# core5.net
KiCad netlist of a schematic drawn in EAGLE
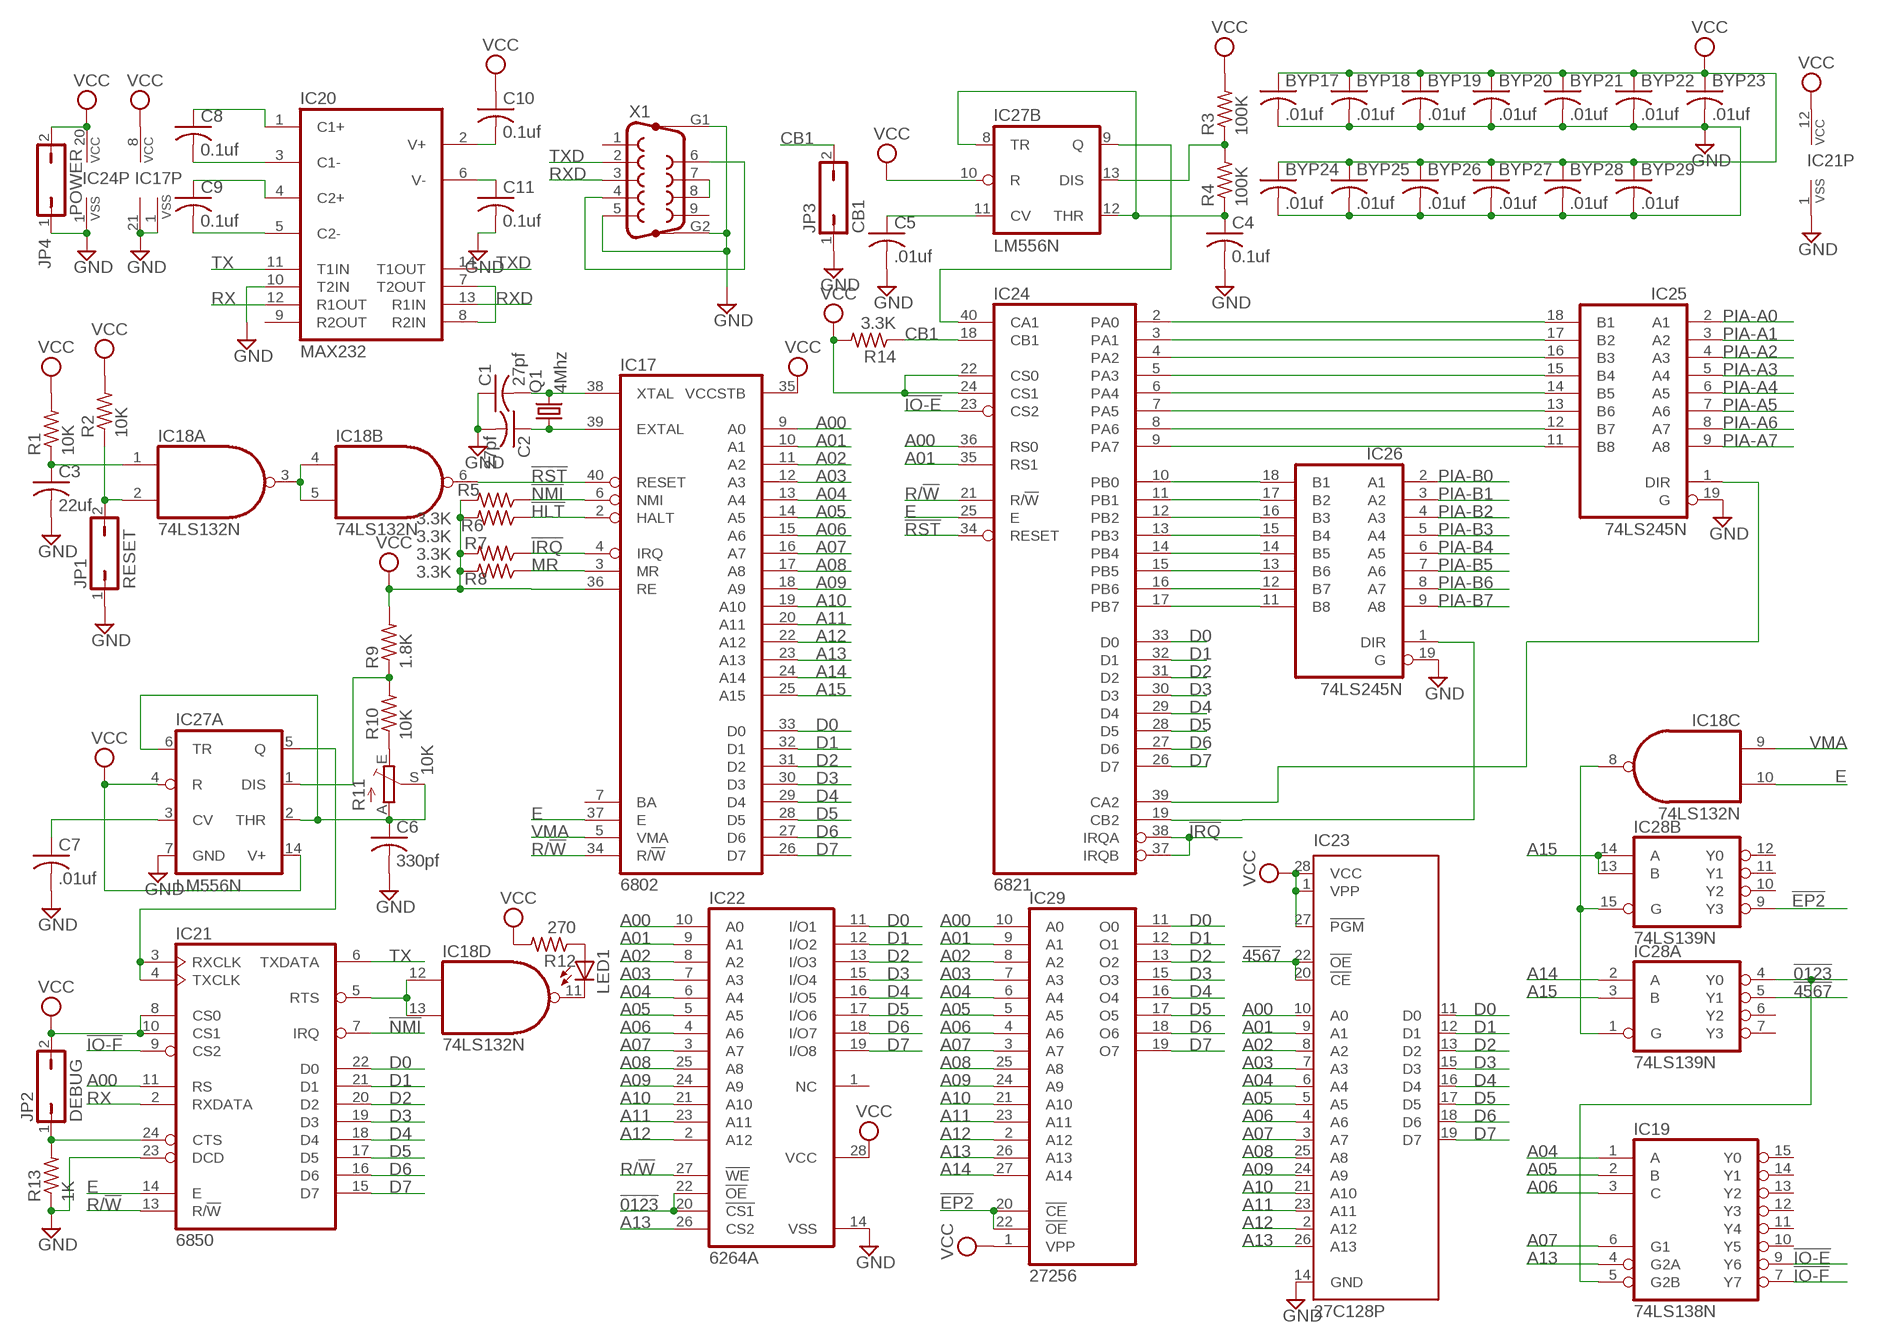
[diagram p0: schematic, sheet 1]
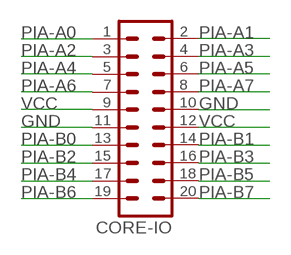
[diagram p1: schematic, sheet 2]

(export (version "E")
  (design (tool "Eeschema 10.0.6"))
  (components
    (comp (ref "CORE-IO")
      (value "MA10-2")
      (footprint "eagle-import:MA10-2")
      (libsource (lib "eagle-import") (part "MA10-2"))
    )
    (comp (ref "BYP17")
      (value ".01uf")
      (footprint "eagle-import:C050-025X075")
      (libsource (lib "eagle-import") (part "C-US050-025X075"))
    )
    (comp (ref "BYP18")
      (value ".01uf")
      (footprint "eagle-import:C050-025X075")
      (libsource (lib "eagle-import") (part "C-US050-025X075"))
    )
    (comp (ref "BYP19")
      (value ".01uf")
      (footprint "eagle-import:C050-025X075")
      (libsource (lib "eagle-import") (part "C-US050-025X075"))
    )
    (comp (ref "BYP20")
      (value ".01uf")
      (footprint "eagle-import:C050-025X075")
      (libsource (lib "eagle-import") (part "C-US050-025X075"))
    )
    (comp (ref "BYP21")
      (value ".01uf")
      (footprint "eagle-import:C050-025X075")
      (libsource (lib "eagle-import") (part "C-US050-025X075"))
    )
    (comp (ref "BYP22")
      (value ".01uf")
      (footprint "eagle-import:C050-025X075")
      (libsource (lib "eagle-import") (part "C-US050-025X075"))
    )
    (comp (ref "BYP23")
      (value ".01uf")
      (footprint "eagle-import:C050-025X075")
      (libsource (lib "eagle-import") (part "C-US050-025X075"))
    )
    (comp (ref "BYP24")
      (value ".01uf")
      (footprint "eagle-import:C050-025X075")
      (libsource (lib "eagle-import") (part "C-US050-025X075"))
    )
    (comp (ref "BYP25")
      (value ".01uf")
      (footprint "eagle-import:C050-025X075")
      (libsource (lib "eagle-import") (part "C-US050-025X075"))
    )
    (comp (ref "BYP26")
      (value ".01uf")
      (footprint "eagle-import:C050-025X075")
      (libsource (lib "eagle-import") (part "C-US050-025X075"))
    )
    (comp (ref "BYP27")
      (value ".01uf")
      (footprint "eagle-import:C050-025X075")
      (libsource (lib "eagle-import") (part "C-US050-025X075"))
    )
    (comp (ref "BYP28")
      (value ".01uf")
      (footprint "eagle-import:C050-025X075")
      (libsource (lib "eagle-import") (part "C-US050-025X075"))
    )
    (comp (ref "BYP29")
      (value ".01uf")
      (footprint "eagle-import:C050-025X075")
      (libsource (lib "eagle-import") (part "C-US050-025X075"))
    )
    (comp (ref "C1")
      (value "27pf")
      (footprint "eagle-import:C050-025X075")
      (libsource (lib "eagle-import") (part "C-US050-025X075"))
    )
    (comp (ref "C2")
      (value "27pf")
      (footprint "eagle-import:C050-025X075")
      (libsource (lib "eagle-import") (part "C-US050-025X075"))
    )
    (comp (ref "C3")
      (value "22uf")
      (footprint "eagle-import:C102-043X133")
      (libsource (lib "eagle-import") (part "C-US102-043X133"))
    )
    (comp (ref "C4")
      (value "0.1uf")
      (footprint "eagle-import:C050-025X075")
      (libsource (lib "eagle-import") (part "C-US050-025X075"))
    )
    (comp (ref "C5")
      (value ".01uf")
      (footprint "eagle-import:C050-025X075")
      (libsource (lib "eagle-import") (part "C-US050-025X075"))
    )
    (comp (ref "C6")
      (value "330pf")
      (footprint "eagle-import:C050-025X075")
      (libsource (lib "eagle-import") (part "C-US050-025X075"))
    )
    (comp (ref "C7")
      (value ".01uf")
      (footprint "eagle-import:C050-025X075")
      (libsource (lib "eagle-import") (part "C-US050-025X075"))
    )
    (comp (ref "C8")
      (value "0.1uf")
      (footprint "eagle-import:C050-025X075")
      (libsource (lib "eagle-import") (part "C-US050-025X075"))
    )
    (comp (ref "C9")
      (value "0.1uf")
      (footprint "eagle-import:C050-025X075")
      (libsource (lib "eagle-import") (part "C-US050-025X075"))
    )
    (comp (ref "C10")
      (value "0.1uf")
      (footprint "eagle-import:C050-025X075")
      (libsource (lib "eagle-import") (part "C-US050-025X075"))
    )
    (comp (ref "C11")
      (value "0.1uf")
      (footprint "eagle-import:C050-025X075")
      (libsource (lib "eagle-import") (part "C-US050-025X075"))
    )
    (comp (ref "IC17")
      (value "6802")
      (footprint "eagle-import:DIL40")
      (libsource (lib "eagle-import") (part "6802"))
    )
    (comp (ref "IC18")
      (value "74LS132N")
      (footprint "eagle-import:DIL14")
      (libsource (lib "eagle-import") (part "7400NLS"))
    )
    (comp (ref "IC19")
      (value "74LS138N")
      (footprint "eagle-import:DIL16")
      (libsource (lib "eagle-import") (part "74138NLS"))
    )
    (comp (ref "IC20")
      (value "MAX232")
      (footprint "eagle-import:DIL16")
      (fields (field (name "MF") "MAXIM") (field (name "MPN") "MAX232ACPE+"))
      (libsource (lib "eagle-import") (part "MAX232"))
    )
    (comp (ref "IC21")
      (value "6850")
      (footprint "eagle-import:DIL24")
      (fields (field (name "MF") "NTE ELECTRONICS") (field (name "MPN") "NTE6850"))
      (libsource (lib "eagle-import") (part "6850"))
    )
    (comp (ref "IC22")
      (value "6264A")
      (footprint "eagle-import:DIL28-6")
      (libsource (lib "eagle-import") (part "6264A"))
    )
    (comp (ref "IC23")
      (value "27C128P")
      (footprint "eagle-import:DIL28-6")
      (libsource (lib "eagle-import") (part "27128PC"))
    )
    (comp (ref "IC24")
      (value "6821")
      (footprint "eagle-import:DIL40")
      (fields (field (name "MF") "NTE ELECTRONICS") (field (name "MPN") "NTE6821"))
      (libsource (lib "eagle-import") (part "6821"))
    )
    (comp (ref "IC25")
      (value "74LS245N")
      (footprint "eagle-import:DIL20")
      (libsource (lib "eagle-import") (part "74245NLS"))
    )
    (comp (ref "IC26")
      (value "74LS245N")
      (footprint "eagle-import:DIL20")
      (libsource (lib "eagle-import") (part "74245NLS"))
    )
    (comp (ref "IC27")
      (value "LM556N")
      (footprint "eagle-import:DIL14")
      (libsource (lib "eagle-import") (part "556NLM"))
    )
    (comp (ref "IC28")
      (value "74LS139N")
      (footprint "eagle-import:DIL16")
      (libsource (lib "eagle-import") (part "74139NLS"))
    )
    (comp (ref "IC29")
      (value "27256")
      (footprint "eagle-import:DIL28")
      (libsource (lib "eagle-import") (part "27256"))
    )
    (comp (ref "JP1")
      (value "RESET")
      (footprint "eagle-import:JP1")
      (libsource (lib "eagle-import") (part "JP1Q"))
    )
    (comp (ref "JP2")
      (value "DEBUG")
      (footprint "eagle-import:JP1")
      (libsource (lib "eagle-import") (part "JP1Q"))
    )
    (comp (ref "JP3")
      (value "CB1")
      (footprint "eagle-import:JP1")
      (libsource (lib "eagle-import") (part "JP1Q"))
    )
    (comp (ref "JP4")
      (value "POWER")
      (footprint "eagle-import:JP1")
      (libsource (lib "eagle-import") (part "JP1Q"))
    )
    (comp (ref "LED1")
      (value "LED3MM")
      (footprint "eagle-import:LED3MM")
      (libsource (lib "eagle-import") (part "LED3MM"))
    )
    (comp (ref "Q1")
      (value "4Mhz")
      (footprint "eagle-import:HC18U-V")
      (libsource (lib "eagle-import") (part "CRYSTALHC18U-V"))
    )
    (comp (ref "R1")
      (value "10K")
      (footprint "eagle-import:0207_7")
      (libsource (lib "eagle-import") (part "R-US_0207/7"))
    )
    (comp (ref "R2")
      (value "10K")
      (footprint "eagle-import:0207_7")
      (libsource (lib "eagle-import") (part "R-US_0207/7"))
    )
    (comp (ref "R3")
      (value "100K")
      (footprint "eagle-import:0207_7")
      (libsource (lib "eagle-import") (part "R-US_0207/7"))
    )
    (comp (ref "R4")
      (value "100K")
      (footprint "eagle-import:0207_7")
      (libsource (lib "eagle-import") (part "R-US_0207/7"))
    )
    (comp (ref "R5")
      (value "3.3K")
      (footprint "eagle-import:0207_7")
      (libsource (lib "eagle-import") (part "R-US_0207/7"))
    )
    (comp (ref "R6")
      (value "3.3K")
      (footprint "eagle-import:0207_7")
      (libsource (lib "eagle-import") (part "R-US_0207/7"))
    )
    (comp (ref "R7")
      (value "3.3K")
      (footprint "eagle-import:0207_7")
      (libsource (lib "eagle-import") (part "R-US_0207/7"))
    )
    (comp (ref "R8")
      (value "3.3K")
      (footprint "eagle-import:0207_7")
      (libsource (lib "eagle-import") (part "R-US_0207/7"))
    )
    (comp (ref "R9")
      (value "1.8K")
      (footprint "eagle-import:0207_7")
      (libsource (lib "eagle-import") (part "R-US_0207/7"))
    )
    (comp (ref "R10")
      (value "10K")
      (footprint "eagle-import:0207_7")
      (libsource (lib "eagle-import") (part "R-US_0207/7"))
    )
    (comp (ref "R11")
      (value "10K")
      (footprint "eagle-import:SP19L")
      (libsource (lib "eagle-import") (part "TRIM_EU-B90P"))
    )
    (comp (ref "R12")
      (value "270")
      (footprint "eagle-import:0207_7")
      (libsource (lib "eagle-import") (part "R-US_0207/7"))
    )
    (comp (ref "R13")
      (value "1K")
      (footprint "eagle-import:0207_7")
      (libsource (lib "eagle-import") (part "R-US_0207/7"))
    )
    (comp (ref "R14")
      (value "3.3K")
      (footprint "eagle-import:0207_7")
      (libsource (lib "eagle-import") (part "R-US_0207/7"))
    )
    (comp (ref "X1")
      (value "F09HP")
      (footprint "eagle-import:F09HP")
      (libsource (lib "eagle-import") (part "F09HP"))
    )
  )
  (nets
    (net (code "1") (name "A00") (class "Default")
      (node (ref "IC17") (pin "9") (pinfunction "A0_9") (pintype "output"))
      (node (ref "IC21") (pin "11") (pinfunction "RS_11") (pintype "input"))
      (node (ref "IC22") (pin "10") (pinfunction "A0_10") (pintype "input"))
      (node (ref "IC23") (pin "10") (pinfunction "A0_10") (pintype "input"))
      (node (ref "IC24") (pin "36") (pinfunction "RS0_36") (pintype "input"))
      (node (ref "IC29") (pin "10") (pinfunction "A0_10") (pintype "input"))
    )
    (net (code "2") (name "A01") (class "Default")
      (node (ref "IC17") (pin "10") (pinfunction "A1_10") (pintype "output"))
      (node (ref "IC22") (pin "9") (pinfunction "A1_9") (pintype "input"))
      (node (ref "IC23") (pin "9") (pinfunction "A1_9") (pintype "input"))
      (node (ref "IC24") (pin "35") (pinfunction "RS1_35") (pintype "input"))
      (node (ref "IC29") (pin "9") (pinfunction "A1_9") (pintype "input"))
    )
    (net (code "3") (name "A02") (class "Default")
      (node (ref "IC17") (pin "11") (pinfunction "A2_11") (pintype "output"))
      (node (ref "IC22") (pin "8") (pinfunction "A2_8") (pintype "input"))
      (node (ref "IC23") (pin "8") (pinfunction "A2_8") (pintype "input"))
      (node (ref "IC29") (pin "8") (pinfunction "A2_8") (pintype "input"))
    )
    (net (code "4") (name "A03") (class "Default")
      (node (ref "IC17") (pin "12") (pinfunction "A3_12") (pintype "output"))
      (node (ref "IC22") (pin "7") (pinfunction "A3_7") (pintype "input"))
      (node (ref "IC23") (pin "7") (pinfunction "A3_7") (pintype "input"))
      (node (ref "IC29") (pin "7") (pinfunction "A3_7") (pintype "input"))
    )
    (net (code "5") (name "A04") (class "Default")
      (node (ref "IC17") (pin "13") (pinfunction "A4_13") (pintype "output"))
      (node (ref "IC19") (pin "1") (pinfunction "A_1") (pintype "input"))
      (node (ref "IC22") (pin "6") (pinfunction "A4_6") (pintype "input"))
      (node (ref "IC23") (pin "6") (pinfunction "A4_6") (pintype "input"))
      (node (ref "IC29") (pin "6") (pinfunction "A4_6") (pintype "input"))
    )
    (net (code "6") (name "A05") (class "Default")
      (node (ref "IC17") (pin "14") (pinfunction "A5_14") (pintype "output"))
      (node (ref "IC19") (pin "2") (pinfunction "B_2") (pintype "input"))
      (node (ref "IC22") (pin "5") (pinfunction "A5_5") (pintype "input"))
      (node (ref "IC23") (pin "5") (pinfunction "A5_5") (pintype "input"))
      (node (ref "IC29") (pin "5") (pinfunction "A5_5") (pintype "input"))
    )
    (net (code "7") (name "A06") (class "Default")
      (node (ref "IC17") (pin "15") (pinfunction "A6_15") (pintype "output"))
      (node (ref "IC19") (pin "3") (pinfunction "C_3") (pintype "input"))
      (node (ref "IC22") (pin "4") (pinfunction "A6_4") (pintype "input"))
      (node (ref "IC23") (pin "4") (pinfunction "A6_4") (pintype "input"))
      (node (ref "IC29") (pin "4") (pinfunction "A6_4") (pintype "input"))
    )
    (net (code "8") (name "A07") (class "Default")
      (node (ref "IC17") (pin "16") (pinfunction "A7_16") (pintype "output"))
      (node (ref "IC19") (pin "6") (pinfunction "G1_6") (pintype "input"))
      (node (ref "IC22") (pin "3") (pinfunction "A7_3") (pintype "input"))
      (node (ref "IC23") (pin "3") (pinfunction "A7_3") (pintype "input"))
      (node (ref "IC29") (pin "3") (pinfunction "A7_3") (pintype "input"))
    )
    (net (code "9") (name "A08") (class "Default")
      (node (ref "IC17") (pin "17") (pinfunction "A8_17") (pintype "output"))
      (node (ref "IC22") (pin "25") (pinfunction "A8_25") (pintype "input"))
      (node (ref "IC23") (pin "25") (pinfunction "A8_25") (pintype "input"))
      (node (ref "IC29") (pin "25") (pinfunction "A8_25") (pintype "input"))
    )
    (net (code "10") (name "A09") (class "Default")
      (node (ref "IC17") (pin "18") (pinfunction "A9_18") (pintype "output"))
      (node (ref "IC22") (pin "24") (pinfunction "A9_24") (pintype "input"))
      (node (ref "IC23") (pin "24") (pinfunction "A9_24") (pintype "input"))
      (node (ref "IC29") (pin "24") (pinfunction "A9_24") (pintype "input"))
    )
    (net (code "11") (name "A10") (class "Default")
      (node (ref "IC17") (pin "19") (pinfunction "A10_19") (pintype "output"))
      (node (ref "IC22") (pin "21") (pinfunction "A10_21") (pintype "input"))
      (node (ref "IC23") (pin "21") (pinfunction "A10_21") (pintype "input"))
      (node (ref "IC29") (pin "21") (pinfunction "A10_21") (pintype "input"))
    )
    (net (code "12") (name "A11") (class "Default")
      (node (ref "IC17") (pin "20") (pinfunction "A11_20") (pintype "output"))
      (node (ref "IC22") (pin "23") (pinfunction "A11_23") (pintype "input"))
      (node (ref "IC23") (pin "23") (pinfunction "A11_23") (pintype "input"))
      (node (ref "IC29") (pin "23") (pinfunction "A11_23") (pintype "input"))
    )
    (net (code "13") (name "A12") (class "Default")
      (node (ref "IC17") (pin "22") (pinfunction "A12_22") (pintype "output"))
      (node (ref "IC22") (pin "2") (pinfunction "A12_2") (pintype "input"))
      (node (ref "IC23") (pin "2") (pinfunction "A12_2") (pintype "input"))
      (node (ref "IC29") (pin "2") (pinfunction "A12_2") (pintype "input"))
    )
    (net (code "14") (name "A13") (class "Default")
      (node (ref "IC17") (pin "23") (pinfunction "A13_23") (pintype "output"))
      (node (ref "IC19") (pin "4") (pinfunction "G2A_4") (pintype "input"))
      (node (ref "IC22") (pin "26") (pinfunction "CS2_26") (pintype "input"))
      (node (ref "IC23") (pin "26") (pinfunction "A13_26") (pintype "input"))
      (node (ref "IC29") (pin "26") (pinfunction "A13_26") (pintype "input"))
    )
    (net (code "15") (name "A14") (class "Default")
      (node (ref "IC17") (pin "24") (pinfunction "A14_24") (pintype "output"))
      (node (ref "IC28") (pin "2") (pinfunction "A_2") (pintype "input"))
      (node (ref "IC29") (pin "27") (pinfunction "A14_27") (pintype "input"))
    )
    (net (code "16") (name "A15") (class "Default")
      (node (ref "IC17") (pin "25") (pinfunction "A15_25") (pintype "output"))
      (node (ref "IC28") (pin "13") (pinfunction "B_13") (pintype "input"))
      (node (ref "IC28") (pin "14") (pinfunction "A_14") (pintype "input"))
      (node (ref "IC28") (pin "3") (pinfunction "B_3") (pintype "input"))
    )
    (net (code "17") (name "CB1") (class "Default")
      (node (ref "IC24") (pin "18") (pinfunction "CB1_18") (pintype "input"))
      (node (ref "JP3") (pin "2") (pinfunction "2_2") (pintype "passive"))
      (node (ref "R14") (pin "1") (pinfunction "1_1") (pintype "passive"))
    )
    (net (code "18") (name "D0") (class "Default")
      (node (ref "IC17") (pin "33") (pinfunction "D0_33") (pintype "bidirectional"))
      (node (ref "IC21") (pin "22") (pinfunction "D0_22") (pintype "bidirectional"))
      (node (ref "IC22") (pin "11") (pinfunction "I/O1_11") (pintype "bidirectional"))
      (node (ref "IC23") (pin "11") (pinfunction "D0_11") (pintype "tri_state"))
      (node (ref "IC24") (pin "33") (pinfunction "D0_33") (pintype "bidirectional"))
      (node (ref "IC29") (pin "11") (pinfunction "O0_11") (pintype "tri_state"))
    )
    (net (code "19") (name "D1") (class "Default")
      (node (ref "IC17") (pin "32") (pinfunction "D1_32") (pintype "bidirectional"))
      (node (ref "IC21") (pin "21") (pinfunction "D1_21") (pintype "bidirectional"))
      (node (ref "IC22") (pin "12") (pinfunction "I/O2_12") (pintype "bidirectional"))
      (node (ref "IC23") (pin "12") (pinfunction "D1_12") (pintype "tri_state"))
      (node (ref "IC24") (pin "32") (pinfunction "D1_32") (pintype "bidirectional"))
      (node (ref "IC29") (pin "12") (pinfunction "O1_12") (pintype "tri_state"))
    )
    (net (code "20") (name "D2") (class "Default")
      (node (ref "IC17") (pin "31") (pinfunction "D2_31") (pintype "bidirectional"))
      (node (ref "IC21") (pin "20") (pinfunction "D2_20") (pintype "bidirectional"))
      (node (ref "IC22") (pin "13") (pinfunction "I/O3_13") (pintype "bidirectional"))
      (node (ref "IC23") (pin "13") (pinfunction "D2_13") (pintype "tri_state"))
      (node (ref "IC24") (pin "31") (pinfunction "D2_31") (pintype "bidirectional"))
      (node (ref "IC29") (pin "13") (pinfunction "O2_13") (pintype "tri_state"))
    )
    (net (code "21") (name "D3") (class "Default")
      (node (ref "IC17") (pin "30") (pinfunction "D3_30") (pintype "bidirectional"))
      (node (ref "IC21") (pin "19") (pinfunction "D3_19") (pintype "bidirectional"))
      (node (ref "IC22") (pin "15") (pinfunction "I/O4_15") (pintype "bidirectional"))
      (node (ref "IC23") (pin "15") (pinfunction "D3_15") (pintype "tri_state"))
      (node (ref "IC24") (pin "30") (pinfunction "D3_30") (pintype "bidirectional"))
      (node (ref "IC29") (pin "15") (pinfunction "O3_15") (pintype "tri_state"))
    )
    (net (code "22") (name "D4") (class "Default")
      (node (ref "IC17") (pin "29") (pinfunction "D4_29") (pintype "bidirectional"))
      (node (ref "IC21") (pin "18") (pinfunction "D4_18") (pintype "bidirectional"))
      (node (ref "IC22") (pin "16") (pinfunction "I/O5_16") (pintype "bidirectional"))
      (node (ref "IC23") (pin "16") (pinfunction "D4_16") (pintype "tri_state"))
      (node (ref "IC24") (pin "29") (pinfunction "D4_29") (pintype "bidirectional"))
      (node (ref "IC29") (pin "16") (pinfunction "O4_16") (pintype "tri_state"))
    )
    (net (code "23") (name "D5") (class "Default")
      (node (ref "IC17") (pin "28") (pinfunction "D5_28") (pintype "bidirectional"))
      (node (ref "IC21") (pin "17") (pinfunction "D5_17") (pintype "bidirectional"))
      (node (ref "IC22") (pin "17") (pinfunction "I/O6_17") (pintype "bidirectional"))
      (node (ref "IC23") (pin "17") (pinfunction "D5_17") (pintype "tri_state"))
      (node (ref "IC24") (pin "28") (pinfunction "D5_28") (pintype "bidirectional"))
      (node (ref "IC29") (pin "17") (pinfunction "O5_17") (pintype "tri_state"))
    )
    (net (code "24") (name "D6") (class "Default")
      (node (ref "IC17") (pin "27") (pinfunction "D6_27") (pintype "bidirectional"))
      (node (ref "IC21") (pin "16") (pinfunction "D6_16") (pintype "bidirectional"))
      (node (ref "IC22") (pin "18") (pinfunction "I/O7_18") (pintype "bidirectional"))
      (node (ref "IC23") (pin "18") (pinfunction "D6_18") (pintype "tri_state"))
      (node (ref "IC24") (pin "27") (pinfunction "D6_27") (pintype "bidirectional"))
      (node (ref "IC29") (pin "18") (pinfunction "O6_18") (pintype "tri_state"))
    )
    (net (code "25") (name "D7") (class "Default")
      (node (ref "IC17") (pin "26") (pinfunction "D7_26") (pintype "bidirectional"))
      (node (ref "IC21") (pin "15") (pinfunction "D7_15") (pintype "bidirectional"))
      (node (ref "IC22") (pin "19") (pinfunction "I/O8_19") (pintype "bidirectional"))
      (node (ref "IC23") (pin "19") (pinfunction "D7_19") (pintype "tri_state"))
      (node (ref "IC24") (pin "26") (pinfunction "D7_26") (pintype "bidirectional"))
      (node (ref "IC29") (pin "19") (pinfunction "O7_19") (pintype "tri_state"))
    )
    (net (code "26") (name "E") (class "Default")
      (node (ref "IC17") (pin "37") (pinfunction "E_37") (pintype "output"))
      (node (ref "IC18") (pin "10") (pinfunction "I1_10") (pintype "input"))
      (node (ref "IC21") (pin "14") (pinfunction "E_14") (pintype "input"))
      (node (ref "IC24") (pin "25") (pinfunction "E_25") (pintype "input"))
    )
    (net (code "27") (name "GND") (class "Default")
      (node (ref "BYP17") (pin "2") (pinfunction "2_2") (pintype "passive"))
      (node (ref "BYP18") (pin "2") (pinfunction "2_2") (pintype "passive"))
      (node (ref "BYP19") (pin "2") (pinfunction "2_2") (pintype "passive"))
      (node (ref "BYP20") (pin "2") (pinfunction "2_2") (pintype "passive"))
      (node (ref "BYP21") (pin "2") (pinfunction "2_2") (pintype "passive"))
      (node (ref "BYP22") (pin "2") (pinfunction "2_2") (pintype "passive"))
      (node (ref "BYP23") (pin "2") (pinfunction "2_2") (pintype "passive"))
      (node (ref "BYP24") (pin "2") (pinfunction "2_2") (pintype "passive"))
      (node (ref "BYP25") (pin "2") (pinfunction "2_2") (pintype "passive"))
      (node (ref "BYP26") (pin "2") (pinfunction "2_2") (pintype "passive"))
      (node (ref "BYP27") (pin "2") (pinfunction "2_2") (pintype "passive"))
      (node (ref "BYP28") (pin "2") (pinfunction "2_2") (pintype "passive"))
      (node (ref "BYP29") (pin "2") (pinfunction "2_2") (pintype "passive"))
      (node (ref "C1") (pin "1") (pinfunction "1_1") (pintype "passive"))
      (node (ref "C11") (pin "2") (pinfunction "2_2") (pintype "passive"))
      (node (ref "C2") (pin "2") (pinfunction "2_2") (pintype "passive"))
      (node (ref "C3") (pin "2") (pinfunction "2_2") (pintype "passive"))
      (node (ref "C4") (pin "2") (pinfunction "2_2") (pintype "passive"))
      (node (ref "C5") (pin "2") (pinfunction "2_2") (pintype "passive"))
      (node (ref "C6") (pin "2") (pinfunction "2_2") (pintype "passive"))
      (node (ref "C7") (pin "2") (pinfunction "2_2") (pintype "passive"))
      (node (ref "CORE-IO") (pin "10") (pinfunction "10_10") (pintype "passive"))
      (node (ref "CORE-IO") (pin "11") (pinfunction "11_11") (pintype "passive"))
      (node (ref "IC17") (pin "1") (pinfunction "VSS_1") (pintype "power_in"))
      (node (ref "IC17") (pin "21") (pinfunction "VSS_21") (pintype "power_in"))
      (node (ref "IC20") (pin "10") (pinfunction "T2IN_10") (pintype "input"))
      (node (ref "IC21") (pin "1") (pinfunction "VSS_1") (pintype "power_in"))
      (node (ref "IC21") (pin "23") (pinfunction "DCD_23") (pintype "input"))
      (node (ref "IC22") (pin "14") (pinfunction "VSS_14") (pintype "power_in"))
      (node (ref "IC23") (pin "14") (pinfunction "GND_14") (pintype "power_in"))
      (node (ref "IC24") (pin "1") (pinfunction "VSS_1") (pintype "power_in"))
      (node (ref "IC25") (pin "19") (pinfunction "G_19") (pintype "input"))
      (node (ref "IC26") (pin "19") (pinfunction "G_19") (pintype "input"))
      (node (ref "IC27") (pin "7") (pinfunction "GND_7") (pintype "power_in"))
      (node (ref "JP1") (pin "1") (pinfunction "1_1") (pintype "passive"))
      (node (ref "JP3") (pin "1") (pinfunction "1_1") (pintype "passive"))
      (node (ref "JP4") (pin "1") (pinfunction "1_1") (pintype "passive"))
      (node (ref "R13") (pin "1") (pinfunction "1_1") (pintype "passive"))
      (node (ref "X1") (pin "5") (pinfunction "5_5") (pintype "passive"))
      (node (ref "X1") (pin "G1") (pinfunction "G1_G1") (pintype "passive"))
      (node (ref "X1") (pin "G2") (pinfunction "G2_G2") (pintype "passive"))
    )
    (net (code "28") (name "MR") (class "Default")
      (node (ref "IC17") (pin "3") (pinfunction "MR_3") (pintype "input"))
      (node (ref "R8") (pin "1") (pinfunction "1_1") (pintype "passive"))
    )
    (net (code "29") (name "Net-(IC17A-EXTAL)") (class "Default")
      (node (ref "C2") (pin "1") (pinfunction "1_1") (pintype "passive"))
      (node (ref "IC17") (pin "39") (pinfunction "EXTAL_39") (pintype "input"))
      (node (ref "Q1") (pin "1") (pinfunction "1_1") (pintype "passive"))
    )
    (net (code "30") (name "Net-(IC17A-XTAL)") (class "Default")
      (node (ref "C1") (pin "2") (pinfunction "2_2") (pintype "passive"))
      (node (ref "IC17") (pin "38") (pinfunction "XTAL_38") (pintype "input"))
      (node (ref "Q1") (pin "2") (pinfunction "2_2") (pintype "passive"))
    )
    (net (code "31") (name "Net-(IC18A-I0)") (class "Default")
      (node (ref "C3") (pin "1") (pinfunction "1_1") (pintype "passive"))
      (node (ref "IC18") (pin "1") (pinfunction "I0_1") (pintype "input"))
      (node (ref "R1") (pin "1") (pinfunction "1_1") (pintype "passive"))
    )
    (net (code "32") (name "Net-(IC18A-I1)") (class "Default")
      (node (ref "IC18") (pin "2") (pinfunction "I1_2") (pintype "input"))
      (node (ref "JP1") (pin "2") (pinfunction "2_2") (pintype "passive"))
      (node (ref "R2") (pin "1") (pinfunction "1_1") (pintype "passive"))
    )
    (net (code "33") (name "Net-(IC18A-O)") (class "Default")
      (node (ref "IC18") (pin "3") (pinfunction "O_3") (pintype "output"))
      (node (ref "IC18") (pin "4") (pinfunction "I0_4") (pintype "input"))
      (node (ref "IC18") (pin "5") (pinfunction "I1_5") (pintype "input"))
    )
    (net (code "34") (name "Net-(IC18C-O)") (class "Default")
      (node (ref "IC18") (pin "8") (pinfunction "O_8") (pintype "output"))
      (node (ref "IC28") (pin "1") (pinfunction "G_1") (pintype "input"))
      (node (ref "IC28") (pin "15") (pinfunction "G_15") (pintype "input"))
    )
    (net (code "35") (name "Net-(IC18D-I0)") (class "Default")
      (node (ref "IC18") (pin "12") (pinfunction "I0_12") (pintype "input"))
      (node (ref "IC18") (pin "13") (pinfunction "I1_13") (pintype "input"))
      (node (ref "IC21") (pin "5") (pinfunction "RTS_5") (pintype "output"))
    )
    (net (code "36") (name "Net-(IC18D-O)") (class "Default")
      (node (ref "IC18") (pin "11") (pinfunction "O_11") (pintype "output"))
      (node (ref "LED1") (pin "K") (pinfunction "C_K") (pintype "passive"))
    )
    (net (code "37") (name "Net-(IC20A-C1+)") (class "Default")
      (node (ref "C8") (pin "1") (pinfunction "1_1") (pintype "passive"))
      (node (ref "IC20") (pin "1") (pinfunction "C1+_1") (pintype "bidirectional"))
    )
    (net (code "38") (name "Net-(IC20A-C1-)") (class "Default")
      (node (ref "C8") (pin "2") (pinfunction "2_2") (pintype "passive"))
      (node (ref "IC20") (pin "3") (pinfunction "C1-_3") (pintype "bidirectional"))
    )
    (net (code "39") (name "Net-(IC20A-C2+)") (class "Default")
      (node (ref "C9") (pin "1") (pinfunction "1_1") (pintype "passive"))
      (node (ref "IC20") (pin "4") (pinfunction "C2+_4") (pintype "bidirectional"))
    )
    (net (code "40") (name "Net-(IC20A-C2-)") (class "Default")
      (node (ref "C9") (pin "2") (pinfunction "2_2") (pintype "passive"))
      (node (ref "IC20") (pin "5") (pinfunction "C2-_5") (pintype "bidirectional"))
    )
    (net (code "41") (name "Net-(IC20A-R2IN)") (class "Default")
      (node (ref "IC20") (pin "7") (pinfunction "T2OUT_7") (pintype "output"))
      (node (ref "IC20") (pin "8") (pinfunction "R2IN_8") (pintype "input"))
    )
    (net (code "42") (name "Net-(IC20A-V+)") (class "Default")
      (node (ref "C10") (pin "2") (pinfunction "2_2") (pintype "passive"))
      (node (ref "IC20") (pin "2") (pinfunction "V+_2") (pintype "bidirectional"))
    )
    (net (code "43") (name "Net-(IC20A-V-)") (class "Default")
      (node (ref "C11") (pin "1") (pinfunction "1_1") (pintype "passive"))
      (node (ref "IC20") (pin "6") (pinfunction "V-_6") (pintype "bidirectional"))
    )
    (net (code "44") (name "Net-(IC21A-CTS)") (class "Default")
      (node (ref "IC21") (pin "24") (pinfunction "CTS_24") (pintype "input"))
      (node (ref "JP2") (pin "1") (pinfunction "1_1") (pintype "passive"))
      (node (ref "R13") (pin "2") (pinfunction "2_2") (pintype "passive"))
    )
    (net (code "45") (name "Net-(IC21A-RXCLK)") (class "Default")
      (node (ref "IC21") (pin "3") (pinfunction "RXCLK_3") (pintype "input"))
      (node (ref "IC21") (pin "4") (pinfunction "TXCLK_4") (pintype "input"))
      (node (ref "IC27") (pin "5") (pinfunction "Q_5") (pintype "output"))
    )
    (net (code "46") (name "Net-(IC24A-CA1)") (class "Default")
      (node (ref "IC24") (pin "40") (pinfunction "CA1_40") (pintype "input"))
      (node (ref "IC27") (pin "9") (pinfunction "Q_9") (pintype "output"))
    )
    (net (code "47") (name "Net-(IC24A-CA2)") (class "Default")
      (node (ref "IC24") (pin "39") (pinfunction "CA2_39") (pintype "bidirectional"))
      (node (ref "IC25") (pin "1") (pinfunction "DIR_1") (pintype "input"))
    )
    (net (code "48") (name "Net-(IC24A-CB2)") (class "Default")
      (node (ref "IC24") (pin "19") (pinfunction "CB2_19") (pintype "bidirectional"))
      (node (ref "IC26") (pin "1") (pinfunction "DIR_1") (pintype "input"))
    )
    (net (code "49") (name "Net-(IC24A-PA0)") (class "Default")
      (node (ref "IC24") (pin "2") (pinfunction "PA0_2") (pintype "bidirectional"))
      (node (ref "IC25") (pin "18") (pinfunction "B1_18") (pintype "bidirectional"))
    )
    (net (code "50") (name "Net-(IC24A-PA1)") (class "Default")
      (node (ref "IC24") (pin "3") (pinfunction "PA1_3") (pintype "bidirectional"))
      (node (ref "IC25") (pin "17") (pinfunction "B2_17") (pintype "bidirectional"))
    )
    (net (code "51") (name "Net-(IC24A-PA2)") (class "Default")
      (node (ref "IC24") (pin "4") (pinfunction "PA2_4") (pintype "bidirectional"))
      (node (ref "IC25") (pin "16") (pinfunction "B3_16") (pintype "bidirectional"))
    )
    (net (code "52") (name "Net-(IC24A-PA3)") (class "Default")
      (node (ref "IC24") (pin "5") (pinfunction "PA3_5") (pintype "bidirectional"))
      (node (ref "IC25") (pin "15") (pinfunction "B4_15") (pintype "bidirectional"))
    )
    (net (code "53") (name "Net-(IC24A-PA4)") (class "Default")
      (node (ref "IC24") (pin "6") (pinfunction "PA4_6") (pintype "bidirectional"))
      (node (ref "IC25") (pin "14") (pinfunction "B5_14") (pintype "bidirectional"))
    )
    (net (code "54") (name "Net-(IC24A-PA5)") (class "Default")
      (node (ref "IC24") (pin "7") (pinfunction "PA5_7") (pintype "bidirectional"))
      (node (ref "IC25") (pin "13") (pinfunction "B6_13") (pintype "bidirectional"))
    )
    (net (code "55") (name "Net-(IC24A-PA6)") (class "Default")
      (node (ref "IC24") (pin "8") (pinfunction "PA6_8") (pintype "bidirectional"))
      (node (ref "IC25") (pin "12") (pinfunction "B7_12") (pintype "bidirectional"))
    )
    (net (code "56") (name "Net-(IC24A-PA7)") (class "Default")
      (node (ref "IC24") (pin "9") (pinfunction "PA7_9") (pintype "bidirectional"))
      (node (ref "IC25") (pin "11") (pinfunction "B8_11") (pintype "bidirectional"))
    )
    (net (code "57") (name "Net-(IC24A-PB0)") (class "Default")
      (node (ref "IC24") (pin "10") (pinfunction "PB0_10") (pintype "bidirectional"))
      (node (ref "IC26") (pin "18") (pinfunction "B1_18") (pintype "bidirectional"))
    )
    (net (code "58") (name "Net-(IC24A-PB1)") (class "Default")
      (node (ref "IC24") (pin "11") (pinfunction "PB1_11") (pintype "bidirectional"))
      (node (ref "IC26") (pin "17") (pinfunction "B2_17") (pintype "bidirectional"))
    )
    (net (code "59") (name "Net-(IC24A-PB2)") (class "Default")
      (node (ref "IC24") (pin "12") (pinfunction "PB2_12") (pintype "bidirectional"))
      (node (ref "IC26") (pin "16") (pinfunction "B3_16") (pintype "bidirectional"))
    )
    (net (code "60") (name "Net-(IC24A-PB3)") (class "Default")
      (node (ref "IC24") (pin "13") (pinfunction "PB3_13") (pintype "bidirectional"))
      (node (ref "IC26") (pin "15") (pinfunction "B4_15") (pintype "bidirectional"))
    )
    (net (code "61") (name "Net-(IC24A-PB4)") (class "Default")
      (node (ref "IC24") (pin "14") (pinfunction "PB4_14") (pintype "bidirectional"))
      (node (ref "IC26") (pin "14") (pinfunction "B5_14") (pintype "bidirectional"))
    )
    (net (code "62") (name "Net-(IC24A-PB5)") (class "Default")
      (node (ref "IC24") (pin "15") (pinfunction "PB5_15") (pintype "bidirectional"))
      (node (ref "IC26") (pin "13") (pinfunction "B6_13") (pintype "bidirectional"))
    )
    (net (code "63") (name "Net-(IC24A-PB6)") (class "Default")
      (node (ref "IC24") (pin "16") (pinfunction "PB6_16") (pintype "bidirectional"))
      (node (ref "IC26") (pin "12") (pinfunction "B7_12") (pintype "bidirectional"))
    )
    (net (code "64") (name "Net-(IC24A-PB7)") (class "Default")
      (node (ref "IC24") (pin "17") (pinfunction "PB7_17") (pintype "bidirectional"))
      (node (ref "IC26") (pin "11") (pinfunction "B8_11") (pintype "bidirectional"))
    )
    (net (code "65") (name "Net-(IC27A-CV)") (class "Default")
      (node (ref "C7") (pin "1") (pinfunction "1_1") (pintype "passive"))
      (node (ref "IC27") (pin "3") (pinfunction "CV_3") (pintype "input"))
    )
    (net (code "66") (name "Net-(IC27A-DIS)") (class "Default")
      (node (ref "IC27") (pin "1") (pinfunction "DIS_1") (pintype "input"))
      (node (ref "R10") (pin "2") (pinfunction "2_2") (pintype "passive"))
      (node (ref "R9") (pin "1") (pinfunction "1_1") (pintype "passive"))
    )
    (net (code "67") (name "Net-(IC27A-THR)") (class "Default")
      (node (ref "C6") (pin "1") (pinfunction "1_1") (pintype "passive"))
      (node (ref "IC27") (pin "2") (pinfunction "THR_2") (pintype "input"))
      (node (ref "IC27") (pin "6") (pinfunction "TR_6") (pintype "input"))
      (node (ref "R11") (pin "A") (pinfunction "A_A") (pintype "passive"))
      (node (ref "R11") (pin "S") (pinfunction "S_S") (pintype "passive"))
    )
    (net (code "68") (name "Net-(IC27B-CV)") (class "Default")
      (node (ref "C5") (pin "1") (pinfunction "1_1") (pintype "passive"))
      (node (ref "IC27") (pin "11") (pinfunction "CV_11") (pintype "input"))
    )
    (net (code "69") (name "Net-(IC27B-DIS)") (class "Default")
      (node (ref "IC27") (pin "13") (pinfunction "DIS_13") (pintype "input"))
      (node (ref "R3") (pin "1") (pinfunction "1_1") (pintype "passive"))
      (node (ref "R4") (pin "2") (pinfunction "2_2") (pintype "passive"))
    )
    (net (code "70") (name "Net-(IC27B-THR)") (class "Default")
      (node (ref "C4") (pin "1") (pinfunction "1_1") (pintype "passive"))
      (node (ref "IC27") (pin "12") (pinfunction "THR_12") (pintype "input"))
      (node (ref "IC27") (pin "8") (pinfunction "TR_8") (pintype "input"))
      (node (ref "R4") (pin "1") (pinfunction "1_1") (pintype "passive"))
    )
    (net (code "71") (name "Net-(LED1-PadA)") (class "Default")
      (node (ref "LED1") (pin "A") (pinfunction "A_A") (pintype "passive"))
      (node (ref "R12") (pin "1") (pinfunction "1_1") (pintype "passive"))
    )
    (net (code "72") (name "Net-(R10-Pad1)") (class "Default")
      (node (ref "R10") (pin "1") (pinfunction "1_1") (pintype "passive"))
      (node (ref "R11") (pin "E") (pinfunction "E_E") (pintype "passive"))
    )
    (net (code "73") (name "Net-(X1-Pad4)") (class "Default")
      (node (ref "X1") (pin "4") (pinfunction "4_4") (pintype "passive"))
      (node (ref "X1") (pin "6") (pinfunction "6_6") (pintype "passive"))
    )
    (net (code "74") (name "Net-(X1-Pad7)") (class "Default")
      (node (ref "X1") (pin "7") (pinfunction "7_7") (pintype "passive"))
      (node (ref "X1") (pin "8") (pinfunction "8_8") (pintype "passive"))
    )
    (net (code "75") (name "PIA-A0") (class "Default")
      (node (ref "CORE-IO") (pin "1") (pinfunction "1_1") (pintype "passive"))
      (node (ref "IC25") (pin "2") (pinfunction "A1_2") (pintype "bidirectional"))
    )
    (net (code "76") (name "PIA-A1") (class "Default")
      (node (ref "CORE-IO") (pin "2") (pinfunction "2_2") (pintype "passive"))
      (node (ref "IC25") (pin "3") (pinfunction "A2_3") (pintype "bidirectional"))
    )
    (net (code "77") (name "PIA-A2") (class "Default")
      (node (ref "CORE-IO") (pin "3") (pinfunction "3_3") (pintype "passive"))
      (node (ref "IC25") (pin "4") (pinfunction "A3_4") (pintype "bidirectional"))
    )
    (net (code "78") (name "PIA-A3") (class "Default")
      (node (ref "CORE-IO") (pin "4") (pinfunction "4_4") (pintype "passive"))
      (node (ref "IC25") (pin "5") (pinfunction "A4_5") (pintype "bidirectional"))
    )
    (net (code "79") (name "PIA-A4") (class "Default")
      (node (ref "CORE-IO") (pin "5") (pinfunction "5_5") (pintype "passive"))
      (node (ref "IC25") (pin "6") (pinfunction "A5_6") (pintype "bidirectional"))
    )
    (net (code "80") (name "PIA-A5") (class "Default")
      (node (ref "CORE-IO") (pin "6") (pinfunction "6_6") (pintype "passive"))
      (node (ref "IC25") (pin "7") (pinfunction "A6_7") (pintype "bidirectional"))
    )
    (net (code "81") (name "PIA-A6") (class "Default")
      (node (ref "CORE-IO") (pin "7") (pinfunction "7_7") (pintype "passive"))
      (node (ref "IC25") (pin "8") (pinfunction "A7_8") (pintype "bidirectional"))
    )
    (net (code "82") (name "PIA-A7") (class "Default")
      (node (ref "CORE-IO") (pin "8") (pinfunction "8_8") (pintype "passive"))
      (node (ref "IC25") (pin "9") (pinfunction "A8_9") (pintype "bidirectional"))
    )
    (net (code "83") (name "PIA-B0") (class "Default")
      (node (ref "CORE-IO") (pin "13") (pinfunction "13_13") (pintype "passive"))
      (node (ref "IC26") (pin "2") (pinfunction "A1_2") (pintype "bidirectional"))
    )
    (net (code "84") (name "PIA-B1") (class "Default")
      (node (ref "CORE-IO") (pin "14") (pinfunction "14_14") (pintype "passive"))
      (node (ref "IC26") (pin "3") (pinfunction "A2_3") (pintype "bidirectional"))
    )
    (net (code "85") (name "PIA-B2") (class "Default")
      (node (ref "CORE-IO") (pin "15") (pinfunction "15_15") (pintype "passive"))
      (node (ref "IC26") (pin "4") (pinfunction "A3_4") (pintype "bidirectional"))
    )
    (net (code "86") (name "PIA-B3") (class "Default")
      (node (ref "CORE-IO") (pin "16") (pinfunction "16_16") (pintype "passive"))
      (node (ref "IC26") (pin "5") (pinfunction "A4_5") (pintype "bidirectional"))
    )
    (net (code "87") (name "PIA-B4") (class "Default")
      (node (ref "CORE-IO") (pin "17") (pinfunction "17_17") (pintype "passive"))
      (node (ref "IC26") (pin "6") (pinfunction "A5_6") (pintype "bidirectional"))
    )
    (net (code "88") (name "PIA-B5") (class "Default")
      (node (ref "CORE-IO") (pin "18") (pinfunction "18_18") (pintype "passive"))
      (node (ref "IC26") (pin "7") (pinfunction "A6_7") (pintype "bidirectional"))
    )
    (net (code "89") (name "PIA-B6") (class "Default")
      (node (ref "CORE-IO") (pin "19") (pinfunction "19_19") (pintype "passive"))
      (node (ref "IC26") (pin "8") (pinfunction "A7_8") (pintype "bidirectional"))
    )
    (net (code "90") (name "PIA-B7") (class "Default")
      (node (ref "CORE-IO") (pin "20") (pinfunction "20_20") (pintype "passive"))
      (node (ref "IC26") (pin "9") (pinfunction "A8_9") (pintype "bidirectional"))
    )
    (net (code "91") (name "RX") (class "Default")
      (node (ref "IC20") (pin "12") (pinfunction "R1OUT_12") (pintype "output"))
      (node (ref "IC21") (pin "2") (pinfunction "RXDATA_2") (pintype "input"))
    )
    (net (code "92") (name "RXD") (class "Default")
      (node (ref "IC20") (pin "13") (pinfunction "R1IN_13") (pintype "input"))
      (node (ref "X1") (pin "3") (pinfunction "3_3") (pintype "passive"))
    )
    (net (code "93") (name "R{slash}~{W}") (class "Default")
      (node (ref "IC17") (pin "34") (pinfunction "R/~{W}_34") (pintype "output"))
      (node (ref "IC21") (pin "13") (pinfunction "R/~{W}_13") (pintype "input"))
      (node (ref "IC22") (pin "27") (pinfunction "~{WE}_27") (pintype "input"))
      (node (ref "IC24") (pin "21") (pinfunction "R/~{W}_21") (pintype "input"))
    )
    (net (code "94") (name "TX") (class "Default")
      (node (ref "IC20") (pin "11") (pinfunction "T1IN_11") (pintype "input"))
      (node (ref "IC21") (pin "6") (pinfunction "TXDATA_6") (pintype "output"))
    )
    (net (code "95") (name "TXD") (class "Default")
      (node (ref "IC20") (pin "14") (pinfunction "T1OUT_14") (pintype "output"))
      (node (ref "X1") (pin "2") (pinfunction "2_2") (pintype "passive"))
    )
    (net (code "96") (name "VCC") (class "Default")
      (node (ref "BYP17") (pin "1") (pinfunction "1_1") (pintype "passive"))
      (node (ref "BYP18") (pin "1") (pinfunction "1_1") (pintype "passive"))
      (node (ref "BYP19") (pin "1") (pinfunction "1_1") (pintype "passive"))
      (node (ref "BYP20") (pin "1") (pinfunction "1_1") (pintype "passive"))
      (node (ref "BYP21") (pin "1") (pinfunction "1_1") (pintype "passive"))
      (node (ref "BYP22") (pin "1") (pinfunction "1_1") (pintype "passive"))
      (node (ref "BYP23") (pin "1") (pinfunction "1_1") (pintype "passive"))
      (node (ref "BYP24") (pin "1") (pinfunction "1_1") (pintype "passive"))
      (node (ref "BYP25") (pin "1") (pinfunction "1_1") (pintype "passive"))
      (node (ref "BYP26") (pin "1") (pinfunction "1_1") (pintype "passive"))
      (node (ref "BYP27") (pin "1") (pinfunction "1_1") (pintype "passive"))
      (node (ref "BYP28") (pin "1") (pinfunction "1_1") (pintype "passive"))
      (node (ref "BYP29") (pin "1") (pinfunction "1_1") (pintype "passive"))
      (node (ref "C10") (pin "1") (pinfunction "1_1") (pintype "passive"))
      (node (ref "CORE-IO") (pin "12") (pinfunction "12_12") (pintype "passive"))
      (node (ref "CORE-IO") (pin "9") (pinfunction "9_9") (pintype "passive"))
      (node (ref "IC17") (pin "35") (pinfunction "VCCSTB_35") (pintype "input"))
      (node (ref "IC17") (pin "36") (pinfunction "RE_36") (pintype "input"))
      (node (ref "IC17") (pin "8") (pinfunction "VCC_8") (pintype "power_in"))
      (node (ref "IC21") (pin "10") (pinfunction "CS1_10") (pintype "input"))
      (node (ref "IC21") (pin "12") (pinfunction "VCC_12") (pintype "power_in"))
      (node (ref "IC21") (pin "8") (pinfunction "CS0_8") (pintype "input"))
      (node (ref "IC22") (pin "28") (pinfunction "VCC_28") (pintype "power_in"))
      (node (ref "IC23") (pin "1") (pinfunction "VPP_1") (pintype "input"))
      (node (ref "IC23") (pin "27") (pinfunction "~{PGM}_27") (pintype "passive"))
      (node (ref "IC23") (pin "28") (pinfunction "VCC_28") (pintype "power_in"))
      (node (ref "IC24") (pin "20") (pinfunction "VCC_20") (pintype "power_in"))
      (node (ref "IC24") (pin "22") (pinfunction "CS0_22") (pintype "input"))
      (node (ref "IC24") (pin "24") (pinfunction "CS1_24") (pintype "input"))
      (node (ref "IC27") (pin "10") (pinfunction "R_10") (pintype "input"))
      (node (ref "IC27") (pin "14") (pinfunction "V+_14") (pintype "power_in"))
      (node (ref "IC27") (pin "4") (pinfunction "R_4") (pintype "input"))
      (node (ref "IC29") (pin "1") (pinfunction "VPP_1") (pintype "input"))
      (node (ref "JP2") (pin "2") (pinfunction "2_2") (pintype "passive"))
      (node (ref "JP4") (pin "2") (pinfunction "2_2") (pintype "passive"))
      (node (ref "R1") (pin "2") (pinfunction "2_2") (pintype "passive"))
      (node (ref "R12") (pin "2") (pinfunction "2_2") (pintype "passive"))
      (node (ref "R14") (pin "2") (pinfunction "2_2") (pintype "passive"))
      (node (ref "R2") (pin "2") (pinfunction "2_2") (pintype "passive"))
      (node (ref "R3") (pin "2") (pinfunction "2_2") (pintype "passive"))
      (node (ref "R5") (pin "2") (pinfunction "2_2") (pintype "passive"))
      (node (ref "R6") (pin "2") (pinfunction "2_2") (pintype "passive"))
      (node (ref "R7") (pin "2") (pinfunction "2_2") (pintype "passive"))
      (node (ref "R8") (pin "2") (pinfunction "2_2") (pintype "passive"))
      (node (ref "R9") (pin "2") (pinfunction "2_2") (pintype "passive"))
    )
    (net (code "97") (name "VMA") (class "Default")
      (node (ref "IC17") (pin "5") (pinfunction "VMA_5") (pintype "output"))
      (node (ref "IC18") (pin "9") (pinfunction "I0_9") (pintype "input"))
    )
    (net (code "98") (name "unconnected-(IC17A-BA-Pad7)") (class "Default")
      (node (ref "IC17") (pin "7") (pinfunction "BA_7") (pintype "output"))
    )
    (net (code "99") (name "unconnected-(IC19A-Y0-Pad15)") (class "Default")
      (node (ref "IC19") (pin "15") (pinfunction "Y0_15") (pintype "output"))
    )
    (net (code "100") (name "unconnected-(IC19A-Y1-Pad14)") (class "Default")
      (node (ref "IC19") (pin "14") (pinfunction "Y1_14") (pintype "output"))
    )
    (net (code "101") (name "unconnected-(IC19A-Y2-Pad13)") (class "Default")
      (node (ref "IC19") (pin "13") (pinfunction "Y2_13") (pintype "output"))
    )
    (net (code "102") (name "unconnected-(IC19A-Y3-Pad12)") (class "Default")
      (node (ref "IC19") (pin "12") (pinfunction "Y3_12") (pintype "output"))
    )
    (net (code "103") (name "unconnected-(IC19A-Y4-Pad11)") (class "Default")
      (node (ref "IC19") (pin "11") (pinfunction "Y4_11") (pintype "output"))
    )
    (net (code "104") (name "unconnected-(IC19A-Y5-Pad10)") (class "Default")
      (node (ref "IC19") (pin "10") (pinfunction "Y5_10") (pintype "output"))
    )
    (net (code "105") (name "unconnected-(IC20A-R2OUT-Pad9)") (class "Default")
      (node (ref "IC20") (pin "9") (pinfunction "R2OUT_9") (pintype "output"))
    )
    (net (code "106") (name "unconnected-(IC22-NC-Pad1)") (class "Default")
      (node (ref "IC22") (pin "1") (pinfunction "NC_1") (pintype "no_connect"))
    )
    (net (code "107") (name "unconnected-(IC28A-Y2-Pad6)") (class "Default")
      (node (ref "IC28") (pin "6") (pinfunction "Y2_6") (pintype "output"))
    )
    (net (code "108") (name "unconnected-(IC28A-Y3-Pad7)") (class "Default")
      (node (ref "IC28") (pin "7") (pinfunction "Y3_7") (pintype "output"))
    )
    (net (code "109") (name "unconnected-(IC28B-Y0-Pad12)") (class "Default")
      (node (ref "IC28") (pin "12") (pinfunction "Y0_12") (pintype "output"))
    )
    (net (code "110") (name "unconnected-(IC28B-Y1-Pad11)") (class "Default")
      (node (ref "IC28") (pin "11") (pinfunction "Y1_11") (pintype "output"))
    )
    (net (code "111") (name "unconnected-(IC28B-Y2-Pad10)") (class "Default")
      (node (ref "IC28") (pin "10") (pinfunction "Y2_10") (pintype "output"))
    )
    (net (code "112") (name "unconnected-(X1-Pad1)") (class "Default")
      (node (ref "X1") (pin "1") (pinfunction "1_1") (pintype "passive"))
    )
    (net (code "113") (name "unconnected-(X1-Pad9)") (class "Default")
      (node (ref "X1") (pin "9") (pinfunction "9_9") (pintype "passive"))
    )
    (net (code "114") (name "~{0123}") (class "Default")
      (node (ref "IC19") (pin "5") (pinfunction "G2B_5") (pintype "input"))
      (node (ref "IC22") (pin "20") (pinfunction "~{CS1}_20") (pintype "input"))
      (node (ref "IC22") (pin "22") (pinfunction "~{OE}_22") (pintype "input"))
      (node (ref "IC28") (pin "4") (pinfunction "Y0_4") (pintype "output"))
    )
    (net (code "115") (name "~{4567}") (class "Default")
      (node (ref "IC23") (pin "20") (pinfunction "~{CE}_20") (pintype "input"))
      (node (ref "IC23") (pin "22") (pinfunction "~{OE}_22") (pintype "input"))
      (node (ref "IC28") (pin "5") (pinfunction "Y1_5") (pintype "output"))
    )
    (net (code "116") (name "~{EP2}") (class "Default")
      (node (ref "IC28") (pin "9") (pinfunction "Y3_9") (pintype "output"))
      (node (ref "IC29") (pin "20") (pinfunction "~{CE}_20") (pintype "input"))
      (node (ref "IC29") (pin "22") (pinfunction "~{OE}_22") (pintype "input"))
    )
    (net (code "117") (name "~{HLT}") (class "Default")
      (node (ref "IC17") (pin "2") (pinfunction "HALT_2") (pintype "input"))
      (node (ref "R5") (pin "1") (pinfunction "1_1") (pintype "passive"))
    )
    (net (code "118") (name "~{IO-E}") (class "Default")
      (node (ref "IC19") (pin "9") (pinfunction "Y6_9") (pintype "output"))
      (node (ref "IC24") (pin "23") (pinfunction "CS2_23") (pintype "input"))
    )
    (net (code "119") (name "~{IO-F}") (class "Default")
      (node (ref "IC19") (pin "7") (pinfunction "Y7_7") (pintype "output"))
      (node (ref "IC21") (pin "9") (pinfunction "CS2_9") (pintype "input"))
    )
    (net (code "120") (name "~{IRQ}") (class "Default")
      (node (ref "IC17") (pin "4") (pinfunction "IRQ_4") (pintype "input"))
      (node (ref "IC24") (pin "37") (pinfunction "IRQB_37") (pintype "open_collector"))
      (node (ref "IC24") (pin "38") (pinfunction "IRQA_38") (pintype "open_collector"))
      (node (ref "R7") (pin "1") (pinfunction "1_1") (pintype "passive"))
    )
    (net (code "121") (name "~{NMI}") (class "Default")
      (node (ref "IC17") (pin "6") (pinfunction "NMI_6") (pintype "input"))
      (node (ref "IC21") (pin "7") (pinfunction "IRQ_7") (pintype "output"))
      (node (ref "R6") (pin "1") (pinfunction "1_1") (pintype "passive"))
    )
    (net (code "122") (name "~{RST}") (class "Default")
      (node (ref "IC17") (pin "40") (pinfunction "RESET_40") (pintype "input"))
      (node (ref "IC18") (pin "6") (pinfunction "O_6") (pintype "output"))
      (node (ref "IC24") (pin "34") (pinfunction "RESET_34") (pintype "input"))
    )
  )
)
